# pontH.net
KiCad netlist of a schematic drawn in Altium Designer
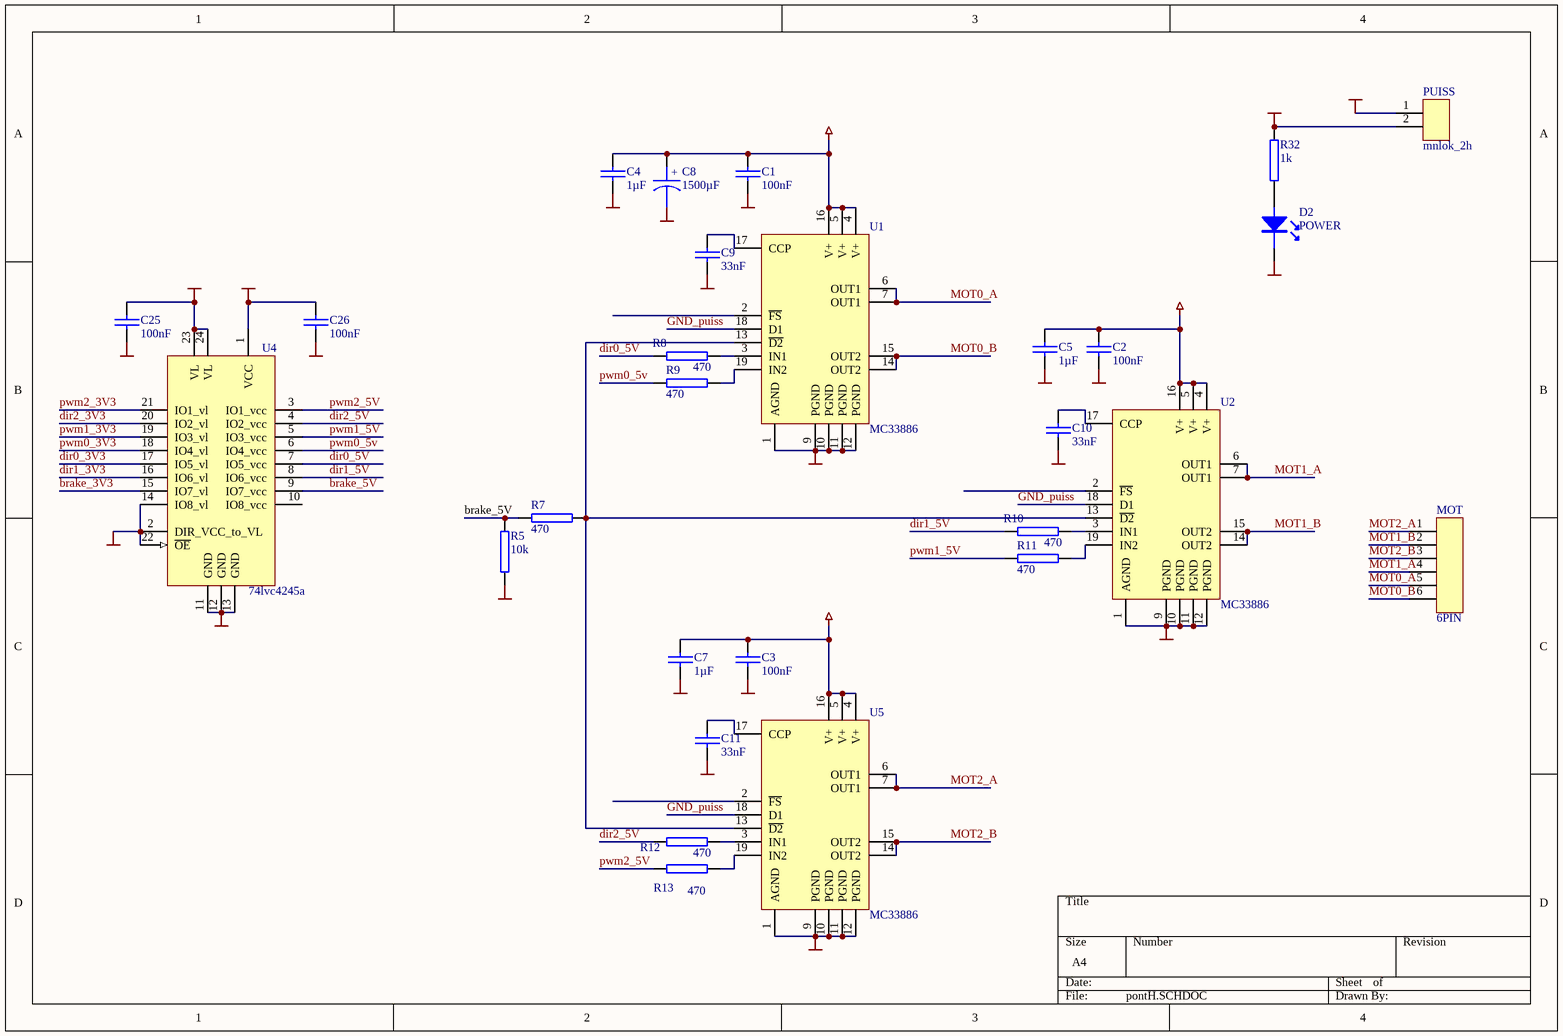
[diagram p0: pontH.SCHDOC]

(export (version "E")
  (design (tool "Eeschema 10.0.6"))
  (components
    (comp (ref "C1") (value "100nF") (footprint "TCONDO") (libsource (lib "*") (part "TCONDO")))
    (comp (ref "C2") (value "100nF") (footprint "TCONDO") (libsource (lib "*") (part "TCONDO")))
    (comp (ref "C3") (value "100nF") (footprint "TCONDO") (libsource (lib "*") (part "TCONDO")))
    (comp (ref "C4") (value "1µF") (footprint "TCONDO") (libsource (lib "*") (part "CONDO")))
    (comp (ref "C5") (value "1µF") (footprint "TCONDO") (libsource (lib "*") (part "CONDO")))
    (comp (ref "C7") (value "1µF") (footprint "TCONDO") (libsource (lib "*") (part "CONDO")))
    (comp (ref "C8")
      (value "1500µF")
      (footprint "CAPA_AXIAL_10_21")
      (libsource (lib "*") (part "CAPACITOR POL"))
    )
    (comp (ref "C9") (value "33nF") (footprint "0805") (libsource (lib "*") (part "TCONDO")))
    (comp (ref "C10") (value "33nF") (footprint "0805") (libsource (lib "*") (part "TCONDO")))
    (comp (ref "C11") (value "33nF") (footprint "0805") (libsource (lib "*") (part "TCONDO")))
    (comp (ref "C25") (value "100nF") (footprint "0805") (libsource (lib "robotter") (part "CONDO")))
    (comp (ref "C26") (value "100nF") (footprint "TCONDO") (libsource (lib "robotter") (part "CONDO")))
    (comp (ref "D2") (value "POWER") (footprint "LED_CMS") (libsource (lib "*") (part "LED_")))
    (comp (ref "MOT")
      (value "6PIN")
      (footprint "con_mat_n_lok_2*3H")
      (libsource (lib "prop2009") (part "6PIN"))
    )
    (comp (ref "PUISS")
      (value "mnlok_2h")
      (footprint "con_mat_n_lok_2h")
      (description "connecteur mat'n-lok 2 voies horizontal")
      (libsource (lib "robotter") (part "con_mat_n_lok_2h"))
    )
    (comp (ref "R5") (value "10k") (footprint "0805") (libsource (lib "*") (part "TRESIST")))
    (comp (ref "R7") (value "470") (footprint "TRES") (libsource (lib "*") (part "TRESIST")))
    (comp (ref "R8") (value "470") (footprint "0805") (libsource (lib "*") (part "TRESIST")))
    (comp (ref "R9") (value "470") (footprint "0805") (libsource (lib "*") (part "TRESIST")))
    (comp (ref "R10") (value "470") (footprint "0805") (libsource (lib "*") (part "TRESIST")))
    (comp (ref "R11") (value "470") (footprint "0805") (libsource (lib "*") (part "TRESIST")))
    (comp (ref "R12") (value "470") (footprint "0805") (libsource (lib "*") (part "TRESIST")))
    (comp (ref "R13") (value "470") (footprint "0805") (libsource (lib "*") (part "TRESIST")))
    (comp (ref "R32") (value "1k") (footprint "0805") (libsource (lib "*") (part "RES")))
    (comp (ref "U1")
      (value "MC33886")
      (footprint "HSOP20")
      (description "pont H 5A")
      (libsource (lib "*") (part "MC33886"))
    )
    (comp (ref "U2")
      (value "MC33886")
      (footprint "HSOP20")
      (description "pont H 5A")
      (libsource (lib "*") (part "MC33886"))
    )
    (comp (ref "U4")
      (value "74lvc4245a")
      (footprint "SSOP24")
      (description "octal voltage transceiver")
      (libsource (lib "prop2009") (part "74ALVC4245"))
    )
    (comp (ref "U5")
      (value "MC33886")
      (footprint "HSOP20")
      (description "pont H 5A")
      (libsource (lib "*") (part "MC33886"))
    )
  )
  (nets
    (net (code "1") (name "+BATT") (class "Default")
      (node (ref "C1") (pin "1") (pintype "passive"))
      (node (ref "C2") (pin "1") (pintype "passive"))
      (node (ref "C3") (pin "1") (pintype "passive"))
      (node (ref "C4") (pin "1") (pintype "passive"))
      (node (ref "C5") (pin "1") (pintype "passive"))
      (node (ref "C7") (pin "1") (pintype "passive"))
      (node (ref "C8") (pin "1") (pinfunction "1_1") (pintype "passive"))
      (node (ref "PUISS") (pin "2") (pinfunction "2_2") (pintype "passive"))
      (node (ref "R32") (pin "2") (pintype "passive"))
      (node (ref "U1") (pin "16") (pinfunction "V+_16") (pintype "passive"))
      (node (ref "U1") (pin "4") (pinfunction "V+_4") (pintype "passive"))
      (node (ref "U1") (pin "5") (pinfunction "V+_5") (pintype "passive"))
      (node (ref "U2") (pin "16") (pinfunction "V+_16") (pintype "passive"))
      (node (ref "U2") (pin "4") (pinfunction "V+_4") (pintype "passive"))
      (node (ref "U2") (pin "5") (pinfunction "V+_5") (pintype "passive"))
      (node (ref "U5") (pin "16") (pinfunction "V+_16") (pintype "passive"))
      (node (ref "U5") (pin "4") (pinfunction "V+_4") (pintype "passive"))
      (node (ref "U5") (pin "5") (pinfunction "V+_5") (pintype "passive"))
    )
    (net (code "2") (name "/MOT0_A") (class "Default")
      (node (ref "MOT") (pin "5") (pinfunction "5_5") (pintype "passive"))
      (node (ref "U1") (pin "6") (pinfunction "OUT1_6") (pintype "passive"))
      (node (ref "U1") (pin "7") (pinfunction "OUT1_7") (pintype "passive"))
    )
    (net (code "3") (name "/MOT0_B") (class "Default")
      (node (ref "MOT") (pin "6") (pinfunction "6_6") (pintype "passive"))
      (node (ref "U1") (pin "14") (pinfunction "OUT2_14") (pintype "passive"))
      (node (ref "U1") (pin "15") (pinfunction "OUT2_15") (pintype "passive"))
    )
    (net (code "4") (name "/MOT1_A") (class "Default")
      (node (ref "MOT") (pin "4") (pinfunction "4_4") (pintype "passive"))
      (node (ref "U2") (pin "6") (pinfunction "OUT1_6") (pintype "passive"))
      (node (ref "U2") (pin "7") (pinfunction "OUT1_7") (pintype "passive"))
    )
    (net (code "5") (name "/MOT1_B") (class "Default")
      (node (ref "MOT") (pin "2") (pinfunction "2_2") (pintype "passive"))
      (node (ref "U2") (pin "14") (pinfunction "OUT2_14") (pintype "passive"))
      (node (ref "U2") (pin "15") (pinfunction "OUT2_15") (pintype "passive"))
    )
    (net (code "6") (name "/MOT2_A") (class "Default")
      (node (ref "MOT") (pin "1") (pinfunction "1_1") (pintype "passive"))
      (node (ref "U5") (pin "6") (pinfunction "OUT1_6") (pintype "passive"))
      (node (ref "U5") (pin "7") (pinfunction "OUT1_7") (pintype "passive"))
    )
    (net (code "7") (name "/MOT2_B") (class "Default")
      (node (ref "MOT") (pin "3") (pinfunction "3_3") (pintype "passive"))
      (node (ref "U5") (pin "14") (pinfunction "OUT2_14") (pintype "passive"))
      (node (ref "U5") (pin "15") (pinfunction "OUT2_15") (pintype "passive"))
    )
    (net (code "8") (name "/brake_3V3") (class "Default")
      (node (ref "U4") (pin "15") (pinfunction "IO7_vl_15") (pintype "passive"))
    )
    (net (code "9") (name "/brake_5V") (class "Default")
      (node (ref "R5") (pin "1") (pintype "passive"))
      (node (ref "R7") (pin "2") (pintype "passive"))
      (node (ref "U4") (pin "9") (pinfunction "IO7_vcc_9") (pintype "passive"))
    )
    (net (code "10") (name "/dir0_3V3") (class "Default")
      (node (ref "U4") (pin "17") (pinfunction "IO5_vl_17") (pintype "passive"))
    )
    (net (code "11") (name "/dir0_5V") (class "Default")
      (node (ref "R8") (pin "1") (pintype "passive"))
      (node (ref "U4") (pin "7") (pinfunction "IO5_vcc_7") (pintype "passive"))
    )
    (net (code "12") (name "/dir1_3V3") (class "Default")
      (node (ref "U4") (pin "16") (pinfunction "IO6_vl_16") (pintype "passive"))
    )
    (net (code "13") (name "/dir1_5V") (class "Default")
      (node (ref "R10") (pin "1") (pintype "passive"))
      (node (ref "U4") (pin "8") (pinfunction "IO6_vcc_8") (pintype "passive"))
    )
    (net (code "14") (name "/dir2_3V3") (class "Default")
      (node (ref "U4") (pin "20") (pinfunction "IO2_vl_20") (pintype "passive"))
    )
    (net (code "15") (name "/dir2_5V") (class "Default")
      (node (ref "R12") (pin "1") (pintype "passive"))
      (node (ref "U4") (pin "4") (pinfunction "IO2_vcc_4") (pintype "passive"))
    )
    (net (code "16") (name "/pwm0_3V3") (class "Default")
      (node (ref "U4") (pin "18") (pinfunction "IO4_vl_18") (pintype "passive"))
    )
    (net (code "17") (name "/pwm0_5v") (class "Default")
      (node (ref "R9") (pin "1") (pintype "passive"))
      (node (ref "U4") (pin "6") (pinfunction "IO4_vcc_6") (pintype "passive"))
    )
    (net (code "18") (name "/pwm1_3V3") (class "Default")
      (node (ref "U4") (pin "19") (pinfunction "IO3_vl_19") (pintype "passive"))
    )
    (net (code "19") (name "/pwm1_5V") (class "Default")
      (node (ref "R11") (pin "1") (pintype "passive"))
      (node (ref "U4") (pin "5") (pinfunction "IO3_vcc_5") (pintype "passive"))
    )
    (net (code "20") (name "/pwm2_3V3") (class "Default")
      (node (ref "U4") (pin "21") (pinfunction "IO1_vl_21") (pintype "passive"))
    )
    (net (code "21") (name "/pwm2_5V") (class "Default")
      (node (ref "R13") (pin "1") (pintype "passive"))
      (node (ref "U4") (pin "3") (pinfunction "IO1_vcc_3") (pintype "passive"))
    )
    (net (code "22") (name "3V3") (class "Default")
      (node (ref "C25") (pin "1") (pintype "passive"))
      (node (ref "U4") (pin "23") (pinfunction "VL_23") (pintype "passive"))
      (node (ref "U4") (pin "24") (pinfunction "VL_24") (pintype "passive"))
    )
    (net (code "23") (name "5V") (class "Default")
      (node (ref "C26") (pin "1") (pintype "passive"))
      (node (ref "U4") (pin "1") (pinfunction "VCC_1") (pintype "passive"))
    )
    (net (code "24") (name "GND") (class "Default")
      (node (ref "C25") (pin "2") (pintype "passive"))
      (node (ref "C26") (pin "2") (pintype "passive"))
      (node (ref "R5") (pin "2") (pintype "passive"))
      (node (ref "U4") (pin "11") (pinfunction "GND_11") (pintype "passive"))
      (node (ref "U4") (pin "12") (pinfunction "GND_12") (pintype "passive"))
      (node (ref "U4") (pin "13") (pinfunction "GND_13") (pintype "passive"))
      (node (ref "U4") (pin "14") (pinfunction "IO8_vl_14") (pintype "passive"))
      (node (ref "U4") (pin "2") (pinfunction "DIR_VCC_to_VL_2") (pintype "passive"))
      (node (ref "U4") (pin "22") (pinfunction "~{OE}_22") (pintype "input"))
    )
    (net (code "25") (name "GND_puiss") (class "Default")
      (node (ref "C1") (pin "2") (pintype "passive"))
      (node (ref "C10") (pin "2") (pintype "passive"))
      (node (ref "C11") (pin "2") (pintype "passive"))
      (node (ref "C2") (pin "2") (pintype "passive"))
      (node (ref "C3") (pin "2") (pintype "passive"))
      (node (ref "C4") (pin "2") (pintype "passive"))
      (node (ref "C5") (pin "2") (pintype "passive"))
      (node (ref "C7") (pin "2") (pintype "passive"))
      (node (ref "C8") (pin "2") (pinfunction "2_2") (pintype "passive"))
      (node (ref "C9") (pin "2") (pintype "passive"))
      (node (ref "D2") (pin "2") (pinfunction "2_2") (pintype "passive"))
      (node (ref "PUISS") (pin "1") (pinfunction "1_1") (pintype "passive"))
      (node (ref "U1") (pin "1") (pinfunction "AGND_1") (pintype "passive"))
      (node (ref "U1") (pin "10") (pinfunction "PGND_10") (pintype "passive"))
      (node (ref "U1") (pin "11") (pinfunction "PGND_11") (pintype "passive"))
      (node (ref "U1") (pin "12") (pinfunction "PGND_12") (pintype "passive"))
      (node (ref "U1") (pin "18") (pinfunction "D1_18") (pintype "passive"))
      (node (ref "U1") (pin "9") (pinfunction "PGND_9") (pintype "passive"))
      (node (ref "U2") (pin "1") (pinfunction "AGND_1") (pintype "passive"))
      (node (ref "U2") (pin "10") (pinfunction "PGND_10") (pintype "passive"))
      (node (ref "U2") (pin "11") (pinfunction "PGND_11") (pintype "passive"))
      (node (ref "U2") (pin "12") (pinfunction "PGND_12") (pintype "passive"))
      (node (ref "U2") (pin "18") (pinfunction "D1_18") (pintype "passive"))
      (node (ref "U2") (pin "9") (pinfunction "PGND_9") (pintype "passive"))
      (node (ref "U5") (pin "1") (pinfunction "AGND_1") (pintype "passive"))
      (node (ref "U5") (pin "10") (pinfunction "PGND_10") (pintype "passive"))
      (node (ref "U5") (pin "11") (pinfunction "PGND_11") (pintype "passive"))
      (node (ref "U5") (pin "12") (pinfunction "PGND_12") (pintype "passive"))
      (node (ref "U5") (pin "18") (pinfunction "D1_18") (pintype "passive"))
      (node (ref "U5") (pin "9") (pinfunction "PGND_9") (pintype "passive"))
    )
    (net (code "26") (name "Net-(D2-Pad1)") (class "Default")
      (node (ref "D2") (pin "1") (pinfunction "1_1") (pintype "passive"))
      (node (ref "R32") (pin "1") (pintype "passive"))
    )
    (net (code "27") (name "Net-(U1-CCP)") (class "Default")
      (node (ref "C9") (pin "1") (pintype "passive"))
      (node (ref "U1") (pin "17") (pinfunction "CCP_17") (pintype "passive"))
    )
    (net (code "28") (name "Net-(U1-IN1)") (class "Default")
      (node (ref "R8") (pin "2") (pintype "passive"))
      (node (ref "U1") (pin "3") (pinfunction "IN1_3") (pintype "passive"))
    )
    (net (code "29") (name "Net-(U1-IN2)") (class "Default")
      (node (ref "R9") (pin "2") (pintype "passive"))
      (node (ref "U1") (pin "19") (pinfunction "IN2_19") (pintype "passive"))
    )
    (net (code "30") (name "Net-(U1-~{D2})") (class "Default")
      (node (ref "R7") (pin "1") (pintype "passive"))
      (node (ref "U1") (pin "13") (pinfunction "~{D2}_13") (pintype "passive"))
      (node (ref "U2") (pin "13") (pinfunction "~{D2}_13") (pintype "passive"))
      (node (ref "U5") (pin "13") (pinfunction "~{D2}_13") (pintype "passive"))
    )
    (net (code "31") (name "Net-(U2-CCP)") (class "Default")
      (node (ref "C10") (pin "1") (pintype "passive"))
      (node (ref "U2") (pin "17") (pinfunction "CCP_17") (pintype "passive"))
    )
    (net (code "32") (name "Net-(U2-IN1)") (class "Default")
      (node (ref "R10") (pin "2") (pintype "passive"))
      (node (ref "U2") (pin "3") (pinfunction "IN1_3") (pintype "passive"))
    )
    (net (code "33") (name "Net-(U2-IN2)") (class "Default")
      (node (ref "R11") (pin "2") (pintype "passive"))
      (node (ref "U2") (pin "19") (pinfunction "IN2_19") (pintype "passive"))
    )
    (net (code "34") (name "Net-(U5-CCP)") (class "Default")
      (node (ref "C11") (pin "1") (pintype "passive"))
      (node (ref "U5") (pin "17") (pinfunction "CCP_17") (pintype "passive"))
    )
    (net (code "35") (name "Net-(U5-IN1)") (class "Default")
      (node (ref "R12") (pin "2") (pintype "passive"))
      (node (ref "U5") (pin "3") (pinfunction "IN1_3") (pintype "passive"))
    )
    (net (code "36") (name "Net-(U5-IN2)") (class "Default")
      (node (ref "R13") (pin "2") (pintype "passive"))
      (node (ref "U5") (pin "19") (pinfunction "IN2_19") (pintype "passive"))
    )
    (net (code "37") (name "unconnected-(U1-~{FS}-Pad2)") (class "Default")
      (node (ref "U1") (pin "2") (pinfunction "~{FS}_2") (pintype "passive"))
    )
    (net (code "38") (name "unconnected-(U2-~{FS}-Pad2)") (class "Default")
      (node (ref "U2") (pin "2") (pinfunction "~{FS}_2") (pintype "passive"))
    )
    (net (code "39") (name "unconnected-(U4-IO8_vcc-Pad10)") (class "Default")
      (node (ref "U4") (pin "10") (pinfunction "IO8_vcc_10") (pintype "passive"))
    )
    (net (code "40") (name "unconnected-(U5-~{FS}-Pad2)") (class "Default")
      (node (ref "U5") (pin "2") (pinfunction "~{FS}_2") (pintype "passive"))
    )
  )
)
